# ESP8266TV.net
KiCad netlist of a schematic drawn in Altium Designer
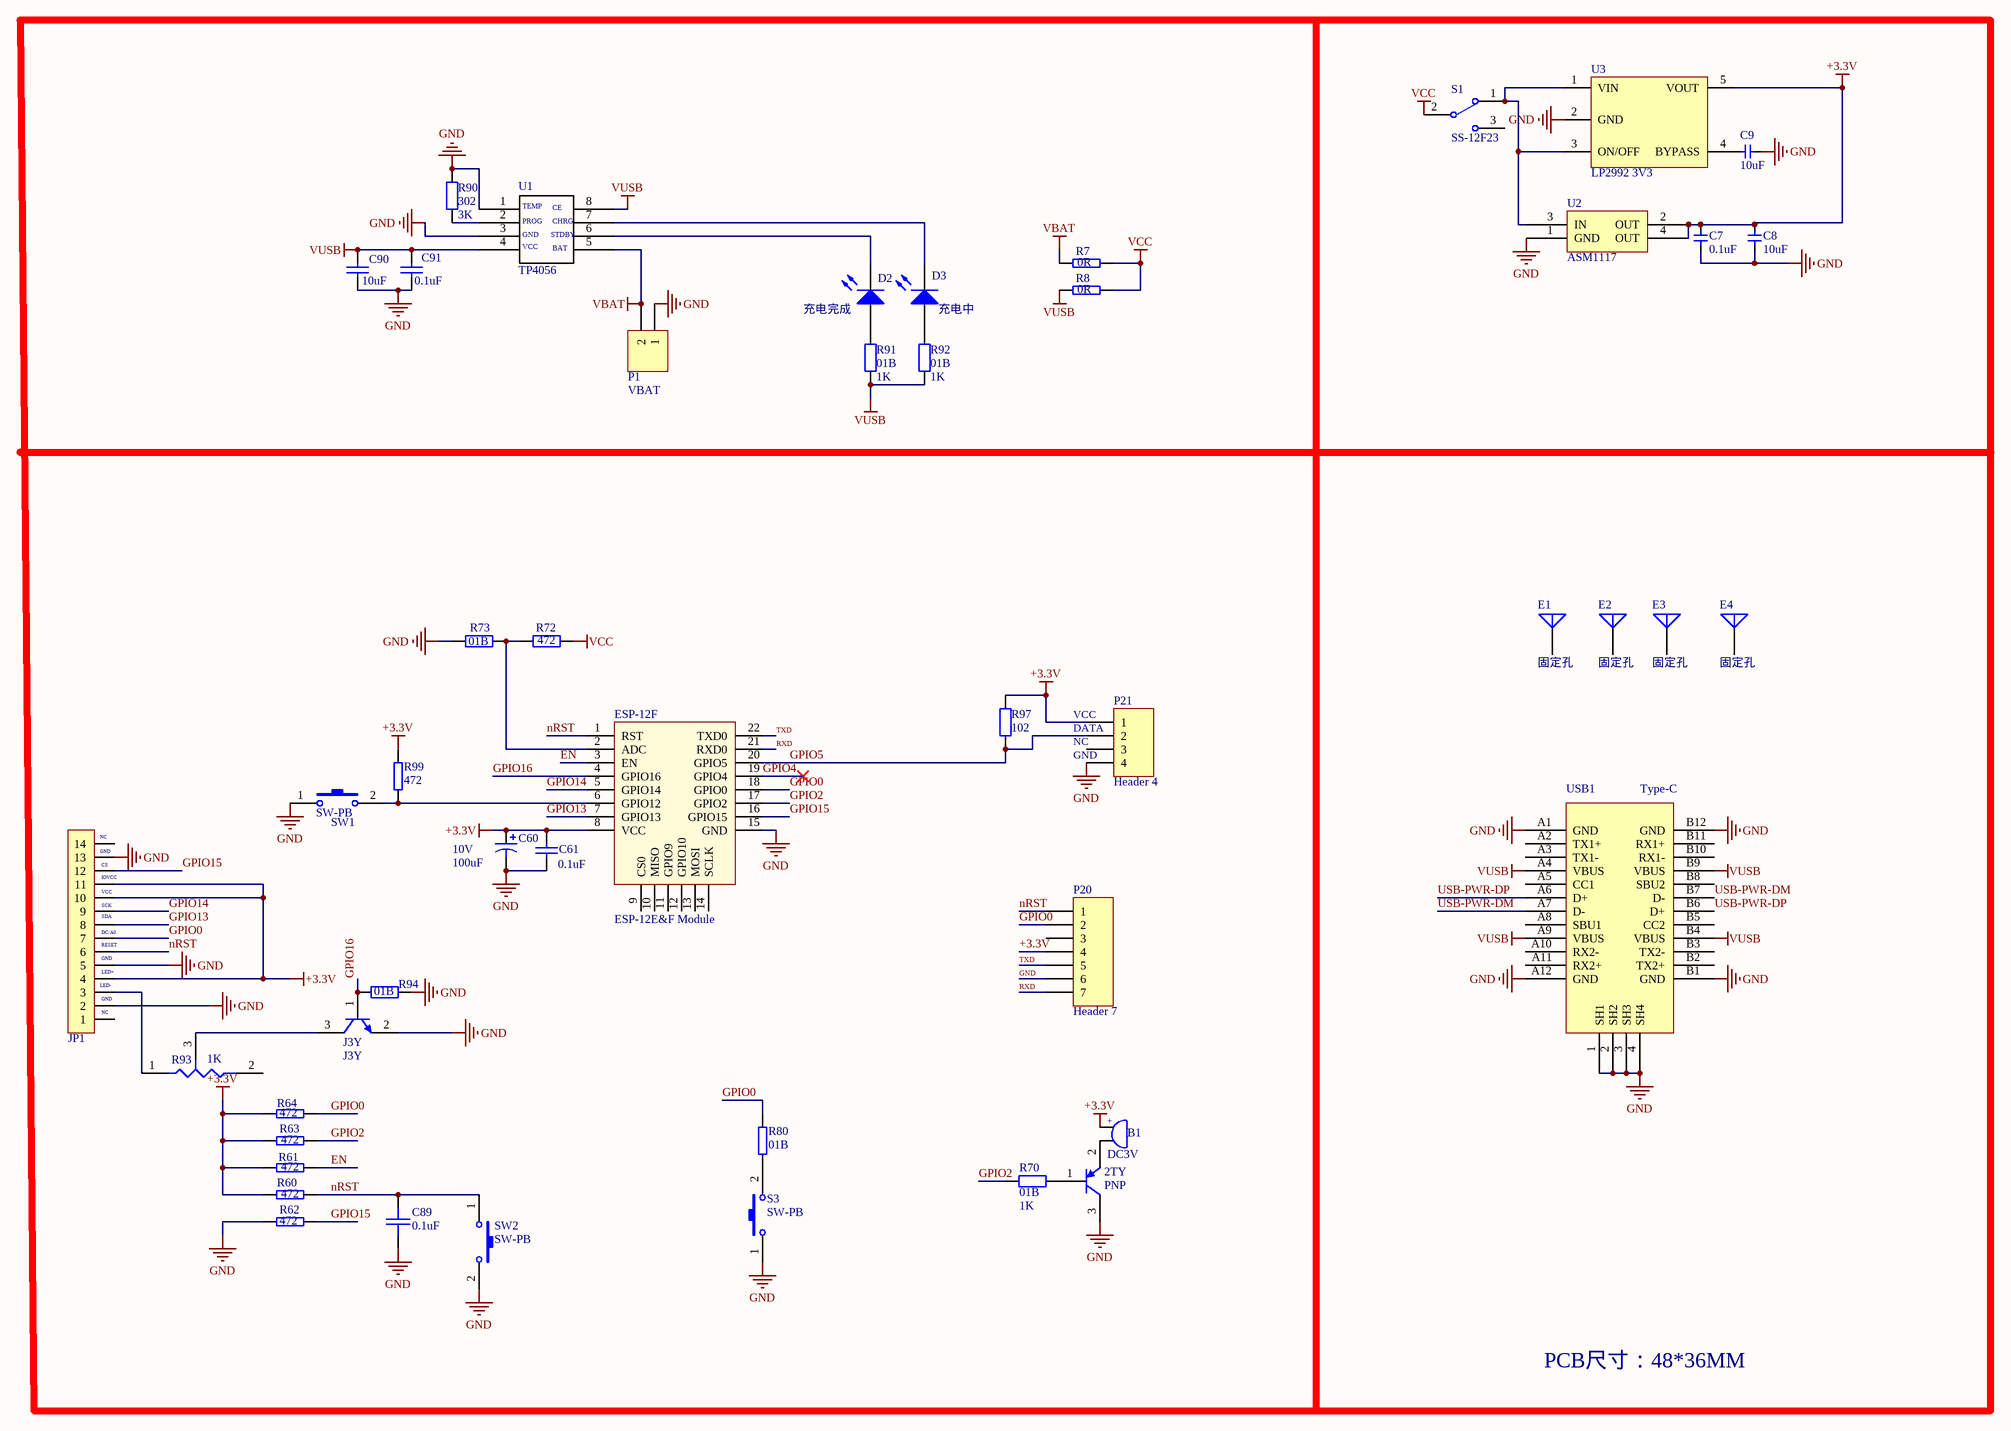
[diagram p0: ESP8266TV.SchDoc]

(export (version "E")
  (design (tool "Eeschema 10.0.6"))
  (components
    (comp (ref "2TY")
      (value "PNP")
      (footprint "2TY")
      (description "PNP Bipolar Transistor")
      (fields (field (name "PUBLISHER") "Altium Limited"))
      (libsource (lib "Miscellaneous Devices") (part "PNP"))
    )
    (comp (ref "B1")
      (value "DC3V")
      (footprint "FM4020")
      (description "蜂鸣器")
      (fields (field (name "版权归属") "源创客"))
      (libsource (lib "未分类器件") (part "BEEP"))
    )
    (comp (ref "C7")
      (value "0.1uF")
      (footprint "0603-1")
      (description "Capacitor")
      (libsource (lib "MyPcbLib") (part "电容-0402"))
    )
    (comp (ref "C8")
      (value "10uF")
      (footprint "0603-1")
      (description "Capacitor")
      (libsource (lib "MyPcbLib") (part "电容-0603"))
    )
    (comp (ref "C9")
      (value "10uF")
      (footprint "0603-1")
      (description "Capacitor")
      (libsource (lib "MyPcbLib") (part "电容-0603"))
    )
    (comp (ref "C60")
      (value "10V")
      (footprint "CM C(5*5.4)")
      (description "Polarized Capacitor (Surface Mount)")
      (fields (field (name "ALTIUM_VALUE") "100uF") (field (name "PUBLISHER") "Altium Limited"))
      (libsource (lib "Miscellaneous Devices") (part "Cap Pol3"))
    )
    (comp (ref "C61")
      (value "0.1uF")
      (footprint "0603-1")
      (description "Capacitor")
      (fields (field (name "PUBLISHER") "Altium Limited"))
      (libsource (lib "Miscellaneous Devices") (part "Cap"))
    )
    (comp (ref "C89")
      (value "0.1uF")
      (footprint "0603-1")
      (description "Surface mount capacitor 0402")
      (libsource (lib "Vowstar_Basic_Device") (part "SMT_C_0402"))
    )
    (comp (ref "C90")
      (value "10uF")
      (footprint "0603-1")
      (description "Capacitor")
      (fields (field (name "PUBLISHER") "Altium Limited"))
      (libsource (lib "Miscellaneous Devices") (part "Cap"))
    )
    (comp (ref "C91")
      (value "0.1uF")
      (footprint "0603-1")
      (description "Capacitor")
      (fields (field (name "PUBLISHER") "Altium Limited"))
      (libsource (lib "Miscellaneous Devices") (part "Cap"))
    )
    (comp (ref "D2")
      (value "~")
      (footprint "LED 0603G")
      (description "Typical INFRARED GaAs LED")
      (fields (field (name "PUBLISHER") "Altium Limited"))
      (libsource (lib "Miscellaneous Devices") (part "LED0"))
    )
    (comp (ref "D3")
      (value "~")
      (footprint "LED 0603R")
      (description "Typical INFRARED GaAs LED")
      (fields (field (name "PUBLISHER") "Altium Limited"))
      (libsource (lib "Miscellaneous Devices") (part "LED0"))
    )
    (comp (ref "E1")
      (value "固定孔")
      (footprint "M2.2 - 3")
      (description "Generic Antenna")
      (fields (field (name "PUBLISHER") "Altium Limited"))
      (libsource (lib "Miscellaneous Devices") (part "Antenna"))
    )
    (comp (ref "E2")
      (value "固定孔")
      (footprint "M2.2 - 3")
      (description "Generic Antenna")
      (fields (field (name "PUBLISHER") "Altium Limited"))
      (libsource (lib "Miscellaneous Devices") (part "Antenna"))
    )
    (comp (ref "E3")
      (value "固定孔")
      (footprint "M2.2 - 3")
      (description "Generic Antenna")
      (fields (field (name "PUBLISHER") "Altium Limited"))
      (libsource (lib "Miscellaneous Devices") (part "Antenna"))
    )
    (comp (ref "E4")
      (value "固定孔")
      (footprint "M2.2 - 3")
      (description "Generic Antenna")
      (fields (field (name "PUBLISHER") "Altium Limited"))
      (libsource (lib "Miscellaneous Devices") (part "Antenna"))
    )
    (comp (ref "ESP-12F")
      (value "ESP-12E&F Module")
      (footprint "ESP-12E&F Module")
      (libsource (lib "ESP-12E&F Module") (part "ESP-12E&F Module"))
    )
    (comp (ref "J3Y")
      (value "J3Y")
      (footprint "J3Y")
      (description "Surface mount NPN transistor, package SOT-23")
      (libsource (lib "Vowstar_Basic_Device") (part "SMT_TRIODE_NPN"))
    )
    (comp (ref "JP1")
      (value "FPC1.0-14P")
      (footprint "FPC0.5 2H-S-W-14P")
      (description "FPC连接器")
      (fields (field (name "版权归属") "源创客"))
      (libsource (lib "FPC连接器") (part "FPC-14P"))
    )
    (comp (ref "P1")
      (value "VBAT")
      (footprint "XH2.54-2P")
      (description "Header, 2-Pin")
      (fields (field (name "PUBLISHER") "Altium Limited"))
      (libsource (lib "Miscellaneous Connectors") (part "Header 2"))
    )
    (comp (ref "P20")
      (value "Header 7")
      (footprint "XH2.54-7P")
      (description "Header, 7-Pin")
      (fields (field (name "PUBLISHER") "Altium Limited"))
      (libsource (lib "Miscellaneous Connectors") (part "Header 7"))
    )
    (comp (ref "P21")
      (value "Header 4")
      (footprint "HDR1X4")
      (description "Header, 4-Pin")
      (fields (field (name "PUBLISHER") "Altium Limited"))
      (libsource (lib "Miscellaneous Connectors") (part "Header 4"))
    )
    (comp (ref "R7")
      (value "0R")
      (footprint "0603-1")
      (description "Surface mount resistor 0402")
      (libsource (lib "Vowstar_Basic_Device") (part "SMT_R_0402"))
    )
    (comp (ref "R8")
      (value "0R")
      (footprint "0603-1")
      (description "Surface mount resistor 0402")
      (libsource (lib "Vowstar_Basic_Device") (part "SMT_R_0402"))
    )
    (comp (ref "R60")
      (value "472")
      (footprint "0603-1")
      (description "Surface mount resistor 0402")
      (libsource (lib "Vowstar_Basic_Device") (part "SMT_R_0402"))
    )
    (comp (ref "R61")
      (value "472")
      (footprint "0603-1")
      (description "Surface mount resistor 0402")
      (libsource (lib "Vowstar_Basic_Device") (part "SMT_R_0402"))
    )
    (comp (ref "R62")
      (value "472")
      (footprint "0603-1")
      (description "Surface mount resistor 0402")
      (libsource (lib "Vowstar_Basic_Device") (part "SMT_R_0402"))
    )
    (comp (ref "R63")
      (value "472")
      (footprint "0603-1")
      (description "Surface mount resistor 0402")
      (libsource (lib "Vowstar_Basic_Device") (part "SMT_R_0402"))
    )
    (comp (ref "R64")
      (value "472")
      (footprint "0603-1")
      (description "Surface mount resistor 0402")
      (libsource (lib "Vowstar_Basic_Device") (part "SMT_R_0402"))
    )
    (comp (ref "R70")
      (value "01B")
      (footprint "0603-1")
      (description "Resistor")
      (fields (field (name "ALTIUM_VALUE") "1K") (field (name "PUBLISHER") "Altium Limited"))
      (libsource (lib "") (part "Res2_3"))
    )
    (comp (ref "R72")
      (value "472")
      (footprint "0603-1")
      (description "Resistor")
      (fields (field (name "PUBLISHER") "Altium Limited"))
      (libsource (lib "") (part "Res2_1"))
    )
    (comp (ref "R73")
      (value "01B")
      (footprint "0603-1")
      (description "Resistor")
      (fields (field (name "PUBLISHER") "Altium Limited"))
      (libsource (lib "") (part "Res2_1"))
    )
    (comp (ref "R80")
      (value "01B")
      (footprint "0603-1")
      (description "Surface mount resistor 0402")
      (libsource (lib "Vowstar_Basic_Device") (part "SMT_R_0402"))
    )
    (comp (ref "R90")
      (value "302")
      (footprint "0603-1")
      (description "Resistor")
      (fields (field (name "ALTIUM_VALUE") "3K") (field (name "PUBLISHER") "Altium Limited"))
      (libsource (lib "") (part "Res2_2"))
    )
    (comp (ref "R91")
      (value "01B")
      (footprint "0603-1")
      (description "Resistor")
      (fields (field (name "ALTIUM_VALUE") "1K") (field (name "PUBLISHER") "Altium Limited"))
      (libsource (lib "Miscellaneous Devices") (part "Res2"))
    )
    (comp (ref "R92")
      (value "01B")
      (footprint "0603-1")
      (description "Resistor")
      (fields (field (name "ALTIUM_VALUE") "1K") (field (name "PUBLISHER") "Altium Limited"))
      (libsource (lib "") (part "Res2_2"))
    )
    (comp (ref "R93")
      (value "1K")
      (footprint "R 3*3")
      (description "Tapped Resistor")
      (fields (field (name "PUBLISHER") "Altium Limited"))
      (libsource (lib "Miscellaneous Devices") (part "Res Tap"))
    )
    (comp (ref "R94")
      (value "01B")
      (footprint "0603-1")
      (description "Resistor")
      (fields (field (name "PUBLISHER") "Altium Limited"))
      (libsource (lib "") (part "Res2_1"))
    )
    (comp (ref "R97")
      (value "102")
      (footprint "0603-1")
      (description "Resistor")
      (fields (field (name "PUBLISHER") "Altium Limited"))
      (libsource (lib "") (part "Res2_2"))
    )
    (comp (ref "R99")
      (value "472")
      (footprint "0603-1")
      (description "Surface mount resistor 0402")
      (libsource (lib "Vowstar_Basic_Device") (part "SMT_R_0402"))
    )
    (comp (ref "S1")
      (value "SS-12F23")
      (footprint "MSK-12C01-07")
      (description "1路波动开关")
      (fields (field (name "版权归属") "源创客"))
      (libsource (lib "按键-开关") (part "SSW-1P"))
    )
    (comp (ref "S3")
      (value "SW-PB")
      (footprint "SW2 _M")
      (description "微动开关")
      (fields (field (name "PUBLISHER") "Altium Limited"))
      (libsource (lib "Schlib2") (part "SW-PB"))
    )
    (comp (ref "SW1")
      (value "SW-PB")
      (footprint "SW2 _M")
      (description "微动开关")
      (fields (field (name "PUBLISHER") "Altium Limited"))
      (libsource (lib "Schlib2") (part "SW-PB"))
    )
    (comp (ref "SW2")
      (value "SW-PB")
      (footprint "SW2 _M")
      (description "微动开关")
      (fields (field (name "PUBLISHER") "Altium Limited"))
      (libsource (lib "Schlib2") (part "SW-PB"))
    )
    (comp (ref "U1") (value "TP4056") (footprint "SOP8_N") (libsource (lib "Schlib1") (part "TP4056")))
    (comp (ref "U2")
      (value "ASM1117")
      (footprint "SOT-223")
      (description "3.3V稳压芯片")
      (libsource (lib "Schlib2") (part "ASM1117"))
    )
    (comp (ref "U3")
      (value "LP2992 3V3")
      (footprint "SOT23-5")
      (description "LDO")
      (libsource (lib "MyPcbLib") (part "LP2992"))
    )
    (comp (ref "USB1")
      (value "Type-C")
      (footprint "USB_TYPE_C_FEMALE_12_16P")
      (libsource (lib "MyPcbLib") (part "USB-Type-C-TOP"))
    )
  )
  (nets
    (net (code "1") (name "+3.3V") (class "Default")
      (node (ref "B1") (pin "1") (pinfunction "1_1") (pintype "passive"))
      (node (ref "C60") (pin "1") (pinfunction "1_1") (pintype "passive"))
      (node (ref "C61") (pin "2") (pinfunction "2_2") (pintype "passive"))
      (node (ref "C7") (pin "2") (pinfunction "2_2") (pintype "passive"))
      (node (ref "C8") (pin "2") (pinfunction "2_2") (pintype "passive"))
      (node (ref "ESP-12F") (pin "8") (pinfunction "VCC_8") (pintype "passive"))
      (node (ref "JP1") (pin "10") (pinfunction "10_10") (pintype "passive"))
      (node (ref "JP1") (pin "11") (pinfunction "11_11") (pintype "passive"))
      (node (ref "JP1") (pin "4") (pinfunction "4_4") (pintype "passive"))
      (node (ref "P20") (pin "4") (pinfunction "4_4") (pintype "passive"))
      (node (ref "P21") (pin "1") (pinfunction "1_1") (pintype "passive"))
      (node (ref "R60") (pin "1") (pinfunction "1_1") (pintype "passive"))
      (node (ref "R61") (pin "1") (pinfunction "1_1") (pintype "passive"))
      (node (ref "R63") (pin "1") (pinfunction "1_1") (pintype "passive"))
      (node (ref "R64") (pin "1") (pinfunction "1_1") (pintype "passive"))
      (node (ref "R97") (pin "1") (pinfunction "1_1") (pintype "passive"))
      (node (ref "R99") (pin "2") (pinfunction "2_2") (pintype "passive"))
      (node (ref "U2") (pin "2") (pinfunction "OUT_2") (pintype "passive"))
      (node (ref "U2") (pin "4") (pinfunction "OUT_4") (pintype "passive"))
      (node (ref "U3") (pin "5") (pinfunction "VOUT_5") (pintype "passive"))
    )
    (net (code "2") (name "/EN") (class "Default")
      (node (ref "ESP-12F") (pin "3") (pinfunction "EN_3") (pintype "passive"))
      (node (ref "R61") (pin "2") (pinfunction "2_2") (pintype "passive"))
    )
    (net (code "3") (name "/GPIO0") (class "Default")
      (node (ref "ESP-12F") (pin "18") (pinfunction "GPIO0_18") (pintype "passive"))
      (node (ref "JP1") (pin "7") (pinfunction "7_7") (pintype "passive"))
      (node (ref "P20") (pin "2") (pinfunction "2_2") (pintype "passive"))
      (node (ref "R64") (pin "2") (pinfunction "2_2") (pintype "passive"))
      (node (ref "R80") (pin "2") (pinfunction "2_2") (pintype "passive"))
    )
    (net (code "4") (name "/GPIO2") (class "Default")
      (node (ref "ESP-12F") (pin "17") (pinfunction "GPIO2_17") (pintype "passive"))
      (node (ref "R63") (pin "2") (pinfunction "2_2") (pintype "passive"))
      (node (ref "R70") (pin "2") (pinfunction "2_2") (pintype "passive"))
    )
    (net (code "5") (name "/GPIO4") (class "Default")
      (node (ref "ESP-12F") (pin "19") (pinfunction "GPIO4_19") (pintype "passive+no_connect"))
    )
    (net (code "6") (name "/GPIO5") (class "Default")
      (node (ref "ESP-12F") (pin "20") (pinfunction "GPIO5_20") (pintype "passive"))
      (node (ref "P21") (pin "2") (pinfunction "2_2") (pintype "passive"))
      (node (ref "R97") (pin "2") (pinfunction "2_2") (pintype "passive"))
    )
    (net (code "7") (name "/GPIO13") (class "Default")
      (node (ref "ESP-12F") (pin "7") (pinfunction "GPIO13_7") (pintype "passive"))
      (node (ref "JP1") (pin "8") (pinfunction "8_8") (pintype "passive"))
    )
    (net (code "8") (name "/GPIO14") (class "Default")
      (node (ref "ESP-12F") (pin "5") (pinfunction "GPIO14_5") (pintype "passive"))
      (node (ref "JP1") (pin "9") (pinfunction "9_9") (pintype "passive"))
    )
    (net (code "9") (name "/GPIO15") (class "Default")
      (node (ref "ESP-12F") (pin "16") (pinfunction "GPIO15_16") (pintype "passive"))
      (node (ref "JP1") (pin "12") (pinfunction "12_12") (pintype "passive"))
      (node (ref "R62") (pin "2") (pinfunction "2_2") (pintype "passive"))
    )
    (net (code "10") (name "/GPIO16") (class "Default")
      (node (ref "ESP-12F") (pin "4") (pinfunction "GPIO16_4") (pintype "passive"))
      (node (ref "J3Y") (pin "1") (pinfunction "B_1") (pintype "passive"))
      (node (ref "R94") (pin "1") (pinfunction "1_1") (pintype "passive"))
    )
    (net (code "11") (name "/RXD") (class "Default")
      (node (ref "ESP-12F") (pin "21") (pinfunction "RXD0_21") (pintype "passive"))
      (node (ref "P20") (pin "7") (pinfunction "7_7") (pintype "passive"))
    )
    (net (code "12") (name "/TXD") (class "Default")
      (node (ref "ESP-12F") (pin "22") (pinfunction "TXD0_22") (pintype "passive"))
      (node (ref "P20") (pin "5") (pinfunction "5_5") (pintype "passive"))
    )
    (net (code "13") (name "/USB-PWR-DM") (class "Default")
      (node (ref "USB1") (pin "A7") (pinfunction "D-_A7") (pintype "passive"))
      (node (ref "USB1") (pin "B7") (pinfunction "D-_B7") (pintype "passive"))
    )
    (net (code "14") (name "/USB-PWR-DP") (class "Default")
      (node (ref "USB1") (pin "A6") (pinfunction "D+_A6") (pintype "passive"))
      (node (ref "USB1") (pin "B6") (pinfunction "D+_B6") (pintype "passive"))
    )
    (net (code "15") (name "/nRST") (class "Default")
      (node (ref "C89") (pin "1") (pinfunction "1_1") (pintype "passive"))
      (node (ref "ESP-12F") (pin "1") (pinfunction "RST_1") (pintype "passive"))
      (node (ref "JP1") (pin "6") (pinfunction "6_6") (pintype "passive"))
      (node (ref "P20") (pin "1") (pinfunction "1_1") (pintype "passive"))
      (node (ref "R60") (pin "2") (pinfunction "2_2") (pintype "passive"))
      (node (ref "SW2") (pin "1") (pinfunction "1_1") (pintype "passive"))
    )
    (net (code "16") (name "GND") (class "Default")
      (node (ref "2TY") (pin "3") (pinfunction "C_3") (pintype "passive"))
      (node (ref "C60") (pin "2") (pinfunction "2_2") (pintype "passive"))
      (node (ref "C61") (pin "1") (pinfunction "1_1") (pintype "passive"))
      (node (ref "C7") (pin "1") (pinfunction "1_1") (pintype "passive"))
      (node (ref "C8") (pin "1") (pinfunction "1_1") (pintype "passive"))
      (node (ref "C89") (pin "2") (pinfunction "2_2") (pintype "passive"))
      (node (ref "C9") (pin "1") (pinfunction "1_1") (pintype "passive"))
      (node (ref "C90") (pin "1") (pinfunction "1_1") (pintype "passive"))
      (node (ref "C91") (pin "1") (pinfunction "1_1") (pintype "passive"))
      (node (ref "ESP-12F") (pin "15") (pinfunction "GND_15") (pintype "passive"))
      (node (ref "J3Y") (pin "2") (pinfunction "E_2") (pintype "passive"))
      (node (ref "JP1") (pin "13") (pinfunction "13_13") (pintype "passive"))
      (node (ref "JP1") (pin "2") (pinfunction "2_2") (pintype "passive"))
      (node (ref "JP1") (pin "5") (pinfunction "5_5") (pintype "passive"))
      (node (ref "P1") (pin "1") (pinfunction "1_1") (pintype "passive"))
      (node (ref "P20") (pin "6") (pinfunction "6_6") (pintype "passive"))
      (node (ref "P21") (pin "4") (pinfunction "4_4") (pintype "passive"))
      (node (ref "R62") (pin "1") (pinfunction "1_1") (pintype "passive"))
      (node (ref "R73") (pin "1") (pinfunction "1_1") (pintype "passive"))
      (node (ref "R90") (pin "1") (pinfunction "1_1") (pintype "passive"))
      (node (ref "R94") (pin "2") (pinfunction "2_2") (pintype "passive"))
      (node (ref "S3") (pin "1") (pinfunction "1_1") (pintype "passive"))
      (node (ref "SW1") (pin "1") (pinfunction "1_1") (pintype "passive"))
      (node (ref "SW2") (pin "2") (pinfunction "2_2") (pintype "passive"))
      (node (ref "U1") (pin "1") (pinfunction "1_1") (pintype "passive"))
      (node (ref "U1") (pin "3") (pinfunction "3_3") (pintype "passive"))
      (node (ref "U2") (pin "1") (pinfunction "GND_1") (pintype "passive"))
      (node (ref "U3") (pin "2") (pinfunction "GND_2") (pintype "passive"))
      (node (ref "USB1") (pin "1") (pinfunction "SH1_1") (pintype "passive"))
      (node (ref "USB1") (pin "2") (pinfunction "SH2_2") (pintype "passive"))
      (node (ref "USB1") (pin "3") (pinfunction "SH3_3") (pintype "passive"))
      (node (ref "USB1") (pin "4") (pinfunction "SH4_4") (pintype "passive"))
      (node (ref "USB1") (pin "A1") (pinfunction "GND_A1") (pintype "passive"))
      (node (ref "USB1") (pin "A12") (pinfunction "GND_A12") (pintype "passive"))
      (node (ref "USB1") (pin "B1") (pinfunction "GND_B1") (pintype "passive"))
      (node (ref "USB1") (pin "B12") (pinfunction "GND_B12") (pintype "passive"))
    )
    (net (code "17") (name "Net-(2TY-B)") (class "Default")
      (node (ref "2TY") (pin "1") (pinfunction "B_1") (pintype "passive"))
      (node (ref "R70") (pin "1") (pinfunction "1_1") (pintype "passive"))
    )
    (net (code "18") (name "Net-(2TY-E)") (class "Default")
      (node (ref "2TY") (pin "2") (pinfunction "E_2") (pintype "passive"))
      (node (ref "B1") (pin "2") (pinfunction "2_2") (pintype "passive"))
    )
    (net (code "19") (name "Net-(D2-A)") (class "Default")
      (node (ref "D2") (pin "1") (pinfunction "A_1") (pintype "passive"))
      (node (ref "R91") (pin "2") (pinfunction "2_2") (pintype "passive"))
    )
    (net (code "20") (name "Net-(D2-K)") (class "Default")
      (node (ref "D2") (pin "2") (pinfunction "K_2") (pintype "passive"))
      (node (ref "U1") (pin "6") (pinfunction "6_6") (pintype "passive"))
    )
    (net (code "21") (name "Net-(D3-A)") (class "Default")
      (node (ref "D3") (pin "1") (pinfunction "A_1") (pintype "passive"))
      (node (ref "R92") (pin "1") (pinfunction "1_1") (pintype "passive"))
    )
    (net (code "22") (name "Net-(D3-K)") (class "Default")
      (node (ref "D3") (pin "2") (pinfunction "K_2") (pintype "passive"))
      (node (ref "U1") (pin "7") (pinfunction "7_7") (pintype "passive"))
    )
    (net (code "23") (name "Net-(ESP-12F-ADC)") (class "Default")
      (node (ref "ESP-12F") (pin "2") (pinfunction "ADC_2") (pintype "passive"))
      (node (ref "R72") (pin "1") (pinfunction "1_1") (pintype "passive"))
      (node (ref "R73") (pin "2") (pinfunction "2_2") (pintype "passive"))
    )
    (net (code "24") (name "Net-(ESP-12F-GPIO12)") (class "Default")
      (node (ref "ESP-12F") (pin "6") (pinfunction "GPIO12_6") (pintype "passive"))
      (node (ref "R99") (pin "1") (pinfunction "1_1") (pintype "passive"))
      (node (ref "SW1") (pin "2") (pinfunction "2_2") (pintype "passive"))
    )
    (net (code "25") (name "Net-(J3Y-C)") (class "Default")
      (node (ref "J3Y") (pin "3") (pinfunction "C_3") (pintype "passive"))
      (node (ref "R93") (pin "3") (pinfunction "TAP_3") (pintype "passive"))
    )
    (net (code "26") (name "Net-(R80-Pad1)") (class "Default")
      (node (ref "R80") (pin "1") (pinfunction "1_1") (pintype "passive"))
      (node (ref "S3") (pin "2") (pinfunction "2_2") (pintype "passive"))
    )
    (net (code "27") (name "Net-(R90-Pad2)") (class "Default")
      (node (ref "R90") (pin "2") (pinfunction "2_2") (pintype "passive"))
      (node (ref "U1") (pin "2") (pinfunction "2_2") (pintype "passive"))
    )
    (net (code "28") (name "Net-(R93-A)") (class "Default")
      (node (ref "JP1") (pin "3") (pinfunction "3_3") (pintype "passive"))
      (node (ref "R93") (pin "1") (pinfunction "A_1") (pintype "passive"))
    )
    (net (code "29") (name "Net-(U2-IN)") (class "Default")
      (node (ref "S1") (pin "1") (pinfunction "1_1") (pintype "passive"))
      (node (ref "U2") (pin "3") (pinfunction "IN_3") (pintype "passive"))
      (node (ref "U3") (pin "1") (pinfunction "VIN_1") (pintype "passive"))
      (node (ref "U3") (pin "3") (pinfunction "ON/OFF_3") (pintype "passive"))
    )
    (net (code "30") (name "Net-(U3-BYPASS)") (class "Default")
      (node (ref "C9") (pin "2") (pinfunction "2_2") (pintype "passive"))
      (node (ref "U3") (pin "4") (pinfunction "BYPASS_4") (pintype "passive"))
    )
    (net (code "31") (name "VBAT") (class "Default")
      (node (ref "P1") (pin "2") (pinfunction "2_2") (pintype "passive"))
      (node (ref "R7") (pin "2") (pinfunction "2_2") (pintype "passive"))
      (node (ref "U1") (pin "5") (pinfunction "5_5") (pintype "passive"))
    )
    (net (code "32") (name "VCC") (class "Default")
      (node (ref "R7") (pin "1") (pinfunction "1_1") (pintype "passive"))
      (node (ref "R72") (pin "2") (pinfunction "2_2") (pintype "passive"))
      (node (ref "R8") (pin "1") (pinfunction "1_1") (pintype "passive"))
      (node (ref "S1") (pin "2") (pinfunction "2_2") (pintype "passive"))
    )
    (net (code "33") (name "VUSB") (class "Default")
      (node (ref "C90") (pin "2") (pinfunction "2_2") (pintype "passive"))
      (node (ref "C91") (pin "2") (pinfunction "2_2") (pintype "passive"))
      (node (ref "R8") (pin "2") (pinfunction "2_2") (pintype "passive"))
      (node (ref "R91") (pin "1") (pinfunction "1_1") (pintype "passive"))
      (node (ref "R92") (pin "2") (pinfunction "2_2") (pintype "passive"))
      (node (ref "U1") (pin "4") (pinfunction "4_4") (pintype "passive"))
      (node (ref "U1") (pin "8") (pinfunction "8_8") (pintype "passive"))
      (node (ref "USB1") (pin "A4") (pinfunction "VBUS_A4") (pintype "passive"))
      (node (ref "USB1") (pin "A9") (pinfunction "VBUS_A9") (pintype "passive"))
      (node (ref "USB1") (pin "B4") (pinfunction "VBUS_B4") (pintype "passive"))
      (node (ref "USB1") (pin "B9") (pinfunction "VBUS_B9") (pintype "passive"))
    )
    (net (code "34") (name "unconnected-(E1-A-Pad1)") (class "Default")
      (node (ref "E1") (pin "1") (pinfunction "A_1") (pintype "passive"))
    )
    (net (code "35") (name "unconnected-(E2-A-Pad1)") (class "Default")
      (node (ref "E2") (pin "1") (pinfunction "A_1") (pintype "passive"))
    )
    (net (code "36") (name "unconnected-(E3-A-Pad1)") (class "Default")
      (node (ref "E3") (pin "1") (pinfunction "A_1") (pintype "passive"))
    )
    (net (code "37") (name "unconnected-(E4-A-Pad1)") (class "Default")
      (node (ref "E4") (pin "1") (pinfunction "A_1") (pintype "passive"))
    )
    (net (code "38") (name "unconnected-(ESP-12F-CS0-Pad9)") (class "Default")
      (node (ref "ESP-12F") (pin "9") (pinfunction "CS0_9") (pintype "passive"))
    )
    (net (code "39") (name "unconnected-(ESP-12F-GPIO9-Pad11)") (class "Default")
      (node (ref "ESP-12F") (pin "11") (pinfunction "GPIO9_11") (pintype "passive"))
    )
    (net (code "40") (name "unconnected-(ESP-12F-GPIO10-Pad12)") (class "Default")
      (node (ref "ESP-12F") (pin "12") (pinfunction "GPIO10_12") (pintype "passive"))
    )
    (net (code "41") (name "unconnected-(ESP-12F-MISO-Pad10)") (class "Default")
      (node (ref "ESP-12F") (pin "10") (pinfunction "MISO_10") (pintype "passive"))
    )
    (net (code "42") (name "unconnected-(ESP-12F-MOSI-Pad13)") (class "Default")
      (node (ref "ESP-12F") (pin "13") (pinfunction "MOSI_13") (pintype "passive"))
    )
    (net (code "43") (name "unconnected-(ESP-12F-SCLK-Pad14)") (class "Default")
      (node (ref "ESP-12F") (pin "14") (pinfunction "SCLK_14") (pintype "passive"))
    )
    (net (code "44") (name "unconnected-(JP1-Pad1)") (class "Default")
      (node (ref "JP1") (pin "1") (pinfunction "1_1") (pintype "passive"))
    )
    (net (code "45") (name "unconnected-(JP1-Pad14)") (class "Default")
      (node (ref "JP1") (pin "14") (pinfunction "14_14") (pintype "passive"))
    )
    (net (code "46") (name "unconnected-(P20-Pad3)") (class "Default")
      (node (ref "P20") (pin "3") (pinfunction "3_3") (pintype "passive"))
    )
    (net (code "47") (name "unconnected-(P21-Pad3)") (class "Default")
      (node (ref "P21") (pin "3") (pinfunction "3_3") (pintype "passive"))
    )
    (net (code "48") (name "unconnected-(R93-B-Pad2)") (class "Default")
      (node (ref "R93") (pin "2") (pinfunction "B_2") (pintype "passive"))
    )
    (net (code "49") (name "unconnected-(S1-Pad3)") (class "Default")
      (node (ref "S1") (pin "3") (pinfunction "3_3") (pintype "passive"))
    )
    (net (code "50") (name "unconnected-(USB1-CC1-PadA5)") (class "Default")
      (node (ref "USB1") (pin "A5") (pinfunction "CC1_A5") (pintype "passive"))
    )
    (net (code "51") (name "unconnected-(USB1-CC2-PadB5)") (class "Default")
      (node (ref "USB1") (pin "B5") (pinfunction "CC2_B5") (pintype "passive"))
    )
    (net (code "52") (name "unconnected-(USB1-RX1+-PadB11)") (class "Default")
      (node (ref "USB1") (pin "B11") (pinfunction "RX1+_B11") (pintype "passive"))
    )
    (net (code "53") (name "unconnected-(USB1-RX1--PadB10)") (class "Default")
      (node (ref "USB1") (pin "B10") (pinfunction "RX1-_B10") (pintype "passive"))
    )
    (net (code "54") (name "unconnected-(USB1-RX2+-PadA11)") (class "Default")
      (node (ref "USB1") (pin "A11") (pinfunction "RX2+_A11") (pintype "passive"))
    )
    (net (code "55") (name "unconnected-(USB1-RX2--PadA10)") (class "Default")
      (node (ref "USB1") (pin "A10") (pinfunction "RX2-_A10") (pintype "passive"))
    )
    (net (code "56") (name "unconnected-(USB1-SBU1-PadA8)") (class "Default")
      (node (ref "USB1") (pin "A8") (pinfunction "SBU1_A8") (pintype "passive"))
    )
    (net (code "57") (name "unconnected-(USB1-SBU2-PadB8)") (class "Default")
      (node (ref "USB1") (pin "B8") (pinfunction "SBU2_B8") (pintype "passive"))
    )
    (net (code "58") (name "unconnected-(USB1-TX1+-PadA2)") (class "Default")
      (node (ref "USB1") (pin "A2") (pinfunction "TX1+_A2") (pintype "passive"))
    )
    (net (code "59") (name "unconnected-(USB1-TX1--PadA3)") (class "Default")
      (node (ref "USB1") (pin "A3") (pinfunction "TX1-_A3") (pintype "passive"))
    )
    (net (code "60") (name "unconnected-(USB1-TX2+-PadB2)") (class "Default")
      (node (ref "USB1") (pin "B2") (pinfunction "TX2+_B2") (pintype "passive"))
    )
    (net (code "61") (name "unconnected-(USB1-TX2--PadB3)") (class "Default")
      (node (ref "USB1") (pin "B3") (pinfunction "TX2-_B3") (pintype "passive"))
    )
  )
)
